# ledboard_smallcon_vert_gndplane.net
KiCad netlist of a schematic drawn in EAGLE
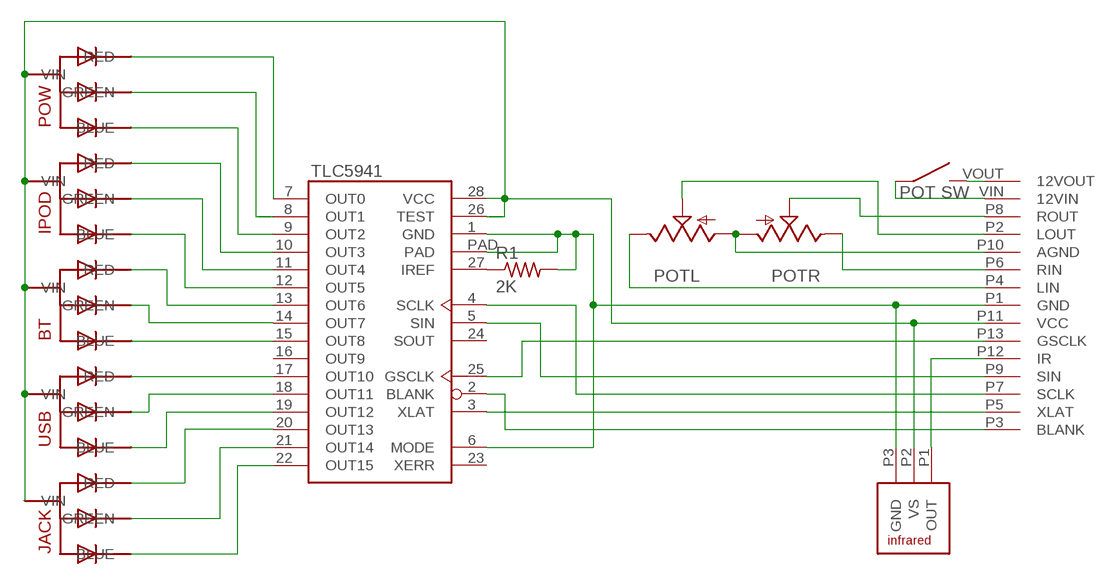
[diagram p0: schematic, sheet 1]

(export (version "E")
  (design (tool "Eeschema 10.0.6"))
  (components
    (comp (ref "BT")
      (value "5MMRGBLEDBENT")
      (footprint "eagle-import:BENTLED")
      (libsource (lib "eagle-import") (part "5MMRGBLEDBENT"))
    )
    (comp (ref "IPOD")
      (value "5MMRGBLEDBENT")
      (footprint "eagle-import:BENTLED")
      (libsource (lib "eagle-import") (part "5MMRGBLEDBENT"))
    )
    (comp (ref "IR")
      (value "TSOP323")
      (footprint "eagle-import:TSOP323")
      (libsource (lib "eagle-import") (part "TSOP323"))
    )
    (comp (ref "JACK")
      (value "5MMRGBLEDBENT")
      (footprint "eagle-import:BENTLED")
      (libsource (lib "eagle-import") (part "5MMRGBLEDBENT"))
    )
    (comp (ref "POT")
      (value "ALPS_RK0971221Z0N")
      (footprint "eagle-import:ALPS_RK0971221Z0X")
      (libsource (lib "eagle-import") (part "ALPS_RK0971221Z0N"))
    )
    (comp (ref "POW")
      (value "5MMRGBLEDBENT")
      (footprint "eagle-import:BENTLED")
      (libsource (lib "eagle-import") (part "5MMRGBLEDBENT"))
    )
    (comp (ref "R1")
      (value "2K")
      (footprint "eagle-import:0207_7")
      (libsource (lib "eagle-import") (part "R-US_0207/7"))
    )
    (comp (ref "U$1")
      (value "TLC5941")
      (footprint "eagle-import:HTSSOP28_POWERPAD")
      (libsource (lib "eagle-import") (part "TLC5941"))
    )
    (comp (ref "U$3")
      (value "CONNECTORSMALL4")
      (footprint "eagle-import:SMALLL4")
      (libsource (lib "eagle-import") (part "CONNECTORSMALL4"))
    )
    (comp (ref "USB")
      (value "5MMRGBLEDBENT")
      (footprint "eagle-import:BENTLED")
      (libsource (lib "eagle-import") (part "5MMRGBLEDBENT"))
    )
  )
  (nets
    (net (code "1") (name "Net-(BT-BLUE)") (class "Default")
      (node (ref "BT") (pin "P$1") (pinfunction "BLUE_P$1") (pintype "bidirectional"))
      (node (ref "U$1") (pin "15") (pinfunction "OUT8_15") (pintype "output"))
    )
    (net (code "2") (name "Net-(BT-GREEN)") (class "Default")
      (node (ref "BT") (pin "P$2") (pinfunction "GREEN_P$2") (pintype "bidirectional"))
      (node (ref "U$1") (pin "14") (pinfunction "OUT7_14") (pintype "output"))
    )
    (net (code "3") (name "Net-(BT-RED)") (class "Default")
      (node (ref "BT") (pin "P$4") (pinfunction "RED_P$4") (pintype "bidirectional"))
      (node (ref "U$1") (pin "13") (pinfunction "OUT6_13") (pintype "output"))
    )
    (net (code "4") (name "Net-(BT-VIN)") (class "Default")
      (node (ref "BT") (pin "P$3") (pinfunction "VIN_P$3") (pintype "bidirectional"))
      (node (ref "IPOD") (pin "P$3") (pinfunction "VIN_P$3") (pintype "bidirectional"))
      (node (ref "IR") (pin "P2") (pinfunction "VS_P2") (pintype "bidirectional"))
      (node (ref "JACK") (pin "P$3") (pinfunction "VIN_P$3") (pintype "bidirectional"))
      (node (ref "POW") (pin "P$3") (pinfunction "VIN_P$3") (pintype "bidirectional"))
      (node (ref "U$1") (pin "26") (pinfunction "TEST_26") (pintype "bidirectional"))
      (node (ref "U$1") (pin "28") (pinfunction "VCC_28") (pintype "power_in"))
      (node (ref "U$3") (pin "P11") (pinfunction "VCC_P11") (pintype "bidirectional"))
      (node (ref "USB") (pin "P$3") (pinfunction "VIN_P$3") (pintype "bidirectional"))
    )
    (net (code "5") (name "Net-(IPOD-BLUE)") (class "Default")
      (node (ref "IPOD") (pin "P$1") (pinfunction "BLUE_P$1") (pintype "bidirectional"))
      (node (ref "U$1") (pin "12") (pinfunction "OUT5_12") (pintype "output"))
    )
    (net (code "6") (name "Net-(IPOD-GREEN)") (class "Default")
      (node (ref "IPOD") (pin "P$2") (pinfunction "GREEN_P$2") (pintype "bidirectional"))
      (node (ref "U$1") (pin "11") (pinfunction "OUT4_11") (pintype "output"))
    )
    (net (code "7") (name "Net-(IPOD-RED)") (class "Default")
      (node (ref "IPOD") (pin "P$4") (pinfunction "RED_P$4") (pintype "bidirectional"))
      (node (ref "U$1") (pin "10") (pinfunction "OUT3_10") (pintype "output"))
    )
    (net (code "8") (name "Net-(IR-GND)") (class "Default")
      (node (ref "IR") (pin "P3") (pinfunction "GND_P3") (pintype "bidirectional"))
      (node (ref "R1") (pin "2") (pinfunction "2_2") (pintype "passive"))
      (node (ref "U$1") (pin "1") (pinfunction "GND_1") (pintype "power_in"))
      (node (ref "U$1") (pin "6") (pinfunction "MODE_6") (pintype "bidirectional"))
      (node (ref "U$1") (pin "PAD") (pinfunction "PAD_PAD") (pintype "bidirectional"))
      (node (ref "U$3") (pin "P1") (pinfunction "GND_P1") (pintype "bidirectional"))
    )
    (net (code "9") (name "Net-(IR-OUT)") (class "Default")
      (node (ref "IR") (pin "P1") (pinfunction "OUT_P1") (pintype "bidirectional"))
      (node (ref "U$3") (pin "P12") (pinfunction "IR_P12") (pintype "bidirectional"))
    )
    (net (code "10") (name "Net-(JACK-BLUE)") (class "Default")
      (node (ref "JACK") (pin "P$1") (pinfunction "BLUE_P$1") (pintype "bidirectional"))
      (node (ref "U$1") (pin "22") (pinfunction "OUT15_22") (pintype "output"))
    )
    (net (code "11") (name "Net-(JACK-GREEN)") (class "Default")
      (node (ref "JACK") (pin "P$2") (pinfunction "GREEN_P$2") (pintype "bidirectional"))
      (node (ref "U$1") (pin "21") (pinfunction "OUT14_21") (pintype "output"))
    )
    (net (code "12") (name "Net-(JACK-RED)") (class "Default")
      (node (ref "JACK") (pin "P$4") (pinfunction "RED_P$4") (pintype "bidirectional"))
      (node (ref "U$1") (pin "20") (pinfunction "OUT13_20") (pintype "output"))
    )
    (net (code "13") (name "Net-(POTB-1)") (class "Default")
      (node (ref "POT") (pin "G1") (pinfunction "1_G1") (pintype "passive"))
      (node (ref "POT") (pin "G2") (pinfunction "1_G2") (pintype "passive"))
      (node (ref "U$3") (pin "P10") (pinfunction "AGND_P10") (pintype "bidirectional"))
    )
    (net (code "14") (name "Net-(POTB-2)") (class "Default")
      (node (ref "POT") (pin "O1") (pinfunction "2_O1") (pintype "passive"))
      (node (ref "U$3") (pin "P2") (pinfunction "LOUT_P2") (pintype "bidirectional"))
    )
    (net (code "15") (name "Net-(POTB-3)") (class "Default")
      (node (ref "POT") (pin "I1") (pinfunction "3_I1") (pintype "passive"))
      (node (ref "U$3") (pin "P4") (pinfunction "LIN_P4") (pintype "bidirectional"))
    )
    (net (code "16") (name "Net-(POTC-2)") (class "Default")
      (node (ref "POT") (pin "O2") (pinfunction "2_O2") (pintype "passive"))
      (node (ref "U$3") (pin "P8") (pinfunction "ROUT_P8") (pintype "bidirectional"))
    )
    (net (code "17") (name "Net-(POTC-3)") (class "Default")
      (node (ref "POT") (pin "I2") (pinfunction "3_I2") (pintype "passive"))
      (node (ref "U$3") (pin "P6") (pinfunction "RIN_P6") (pintype "bidirectional"))
    )
    (net (code "18") (name "Net-(POW-BLUE)") (class "Default")
      (node (ref "POW") (pin "P$1") (pinfunction "BLUE_P$1") (pintype "bidirectional"))
      (node (ref "U$1") (pin "9") (pinfunction "OUT2_9") (pintype "output"))
    )
    (net (code "19") (name "Net-(POW-GREEN)") (class "Default")
      (node (ref "POW") (pin "P$2") (pinfunction "GREEN_P$2") (pintype "bidirectional"))
      (node (ref "U$1") (pin "8") (pinfunction "OUT1_8") (pintype "output"))
    )
    (net (code "20") (name "Net-(POW-RED)") (class "Default")
      (node (ref "POW") (pin "P$4") (pinfunction "RED_P$4") (pintype "bidirectional"))
      (node (ref "U$1") (pin "7") (pinfunction "OUT0_7") (pintype "output"))
    )
    (net (code "21") (name "Net-(U$1-BLANK)") (class "Default")
      (node (ref "U$1") (pin "2") (pinfunction "BLANK_2") (pintype "input"))
      (node (ref "U$3") (pin "P3") (pinfunction "BLANK_P3") (pintype "bidirectional"))
    )
    (net (code "22") (name "Net-(U$1-GSCLK)") (class "Default")
      (node (ref "U$1") (pin "25") (pinfunction "GSCLK_25") (pintype "input"))
      (node (ref "U$3") (pin "P13") (pinfunction "GSCLK_P13") (pintype "bidirectional"))
    )
    (net (code "23") (name "Net-(U$1-IREF)") (class "Default")
      (node (ref "R1") (pin "1") (pinfunction "1_1") (pintype "passive"))
      (node (ref "U$1") (pin "27") (pinfunction "IREF_27") (pintype "input"))
    )
    (net (code "24") (name "Net-(U$1-OUT10)") (class "Default")
      (node (ref "U$1") (pin "17") (pinfunction "OUT10_17") (pintype "output"))
      (node (ref "USB") (pin "P$4") (pinfunction "RED_P$4") (pintype "bidirectional"))
    )
    (net (code "25") (name "Net-(U$1-OUT11)") (class "Default")
      (node (ref "U$1") (pin "18") (pinfunction "OUT11_18") (pintype "output"))
      (node (ref "USB") (pin "P$2") (pinfunction "GREEN_P$2") (pintype "bidirectional"))
    )
    (net (code "26") (name "Net-(U$1-OUT12)") (class "Default")
      (node (ref "U$1") (pin "19") (pinfunction "OUT12_19") (pintype "output"))
      (node (ref "USB") (pin "P$1") (pinfunction "BLUE_P$1") (pintype "bidirectional"))
    )
    (net (code "27") (name "Net-(U$1-SCLK)") (class "Default")
      (node (ref "U$1") (pin "4") (pinfunction "SCLK_4") (pintype "input"))
      (node (ref "U$3") (pin "P7") (pinfunction "SCLK_P7") (pintype "bidirectional"))
    )
    (net (code "28") (name "Net-(U$1-SIN)") (class "Default")
      (node (ref "U$1") (pin "5") (pinfunction "SIN_5") (pintype "input"))
      (node (ref "U$3") (pin "P9") (pinfunction "SIN_P9") (pintype "bidirectional"))
    )
    (net (code "29") (name "Net-(U$1-XLAT)") (class "Default")
      (node (ref "U$1") (pin "3") (pinfunction "XLAT_3") (pintype "input"))
      (node (ref "U$3") (pin "P5") (pinfunction "XLAT_P5") (pintype "bidirectional"))
    )
    (net (code "30") (name "Net-(U$3-12VIN)") (class "Default")
      (node (ref "POT") (pin "S1") (pinfunction "S1_S1") (pintype "power_in"))
      (node (ref "U$3") (pin "VIN") (pinfunction "12VIN_VIN") (pintype "bidirectional"))
    )
    (net (code "31") (name "Net-(U$3-12VOUT)") (class "Default")
      (node (ref "POT") (pin "S2") (pinfunction "S2_S2") (pintype "power_in"))
      (node (ref "U$3") (pin "VOUT") (pinfunction "12VOUT_VOUT") (pintype "bidirectional"))
    )
    (net (code "32") (name "unconnected-(U$1-OUT9-Pad16)") (class "Default")
      (node (ref "U$1") (pin "16") (pinfunction "OUT9_16") (pintype "output"))
    )
    (net (code "33") (name "unconnected-(U$1-SOUT-Pad24)") (class "Default")
      (node (ref "U$1") (pin "24") (pinfunction "SOUT_24") (pintype "output"))
    )
    (net (code "34") (name "unconnected-(U$1-XERR-Pad23)") (class "Default")
      (node (ref "U$1") (pin "23") (pinfunction "XERR_23") (pintype "output"))
    )
  )
)
